# RGMII0_ETH_PHY.net
KiCad netlist of a schematic drawn in Altium Designer
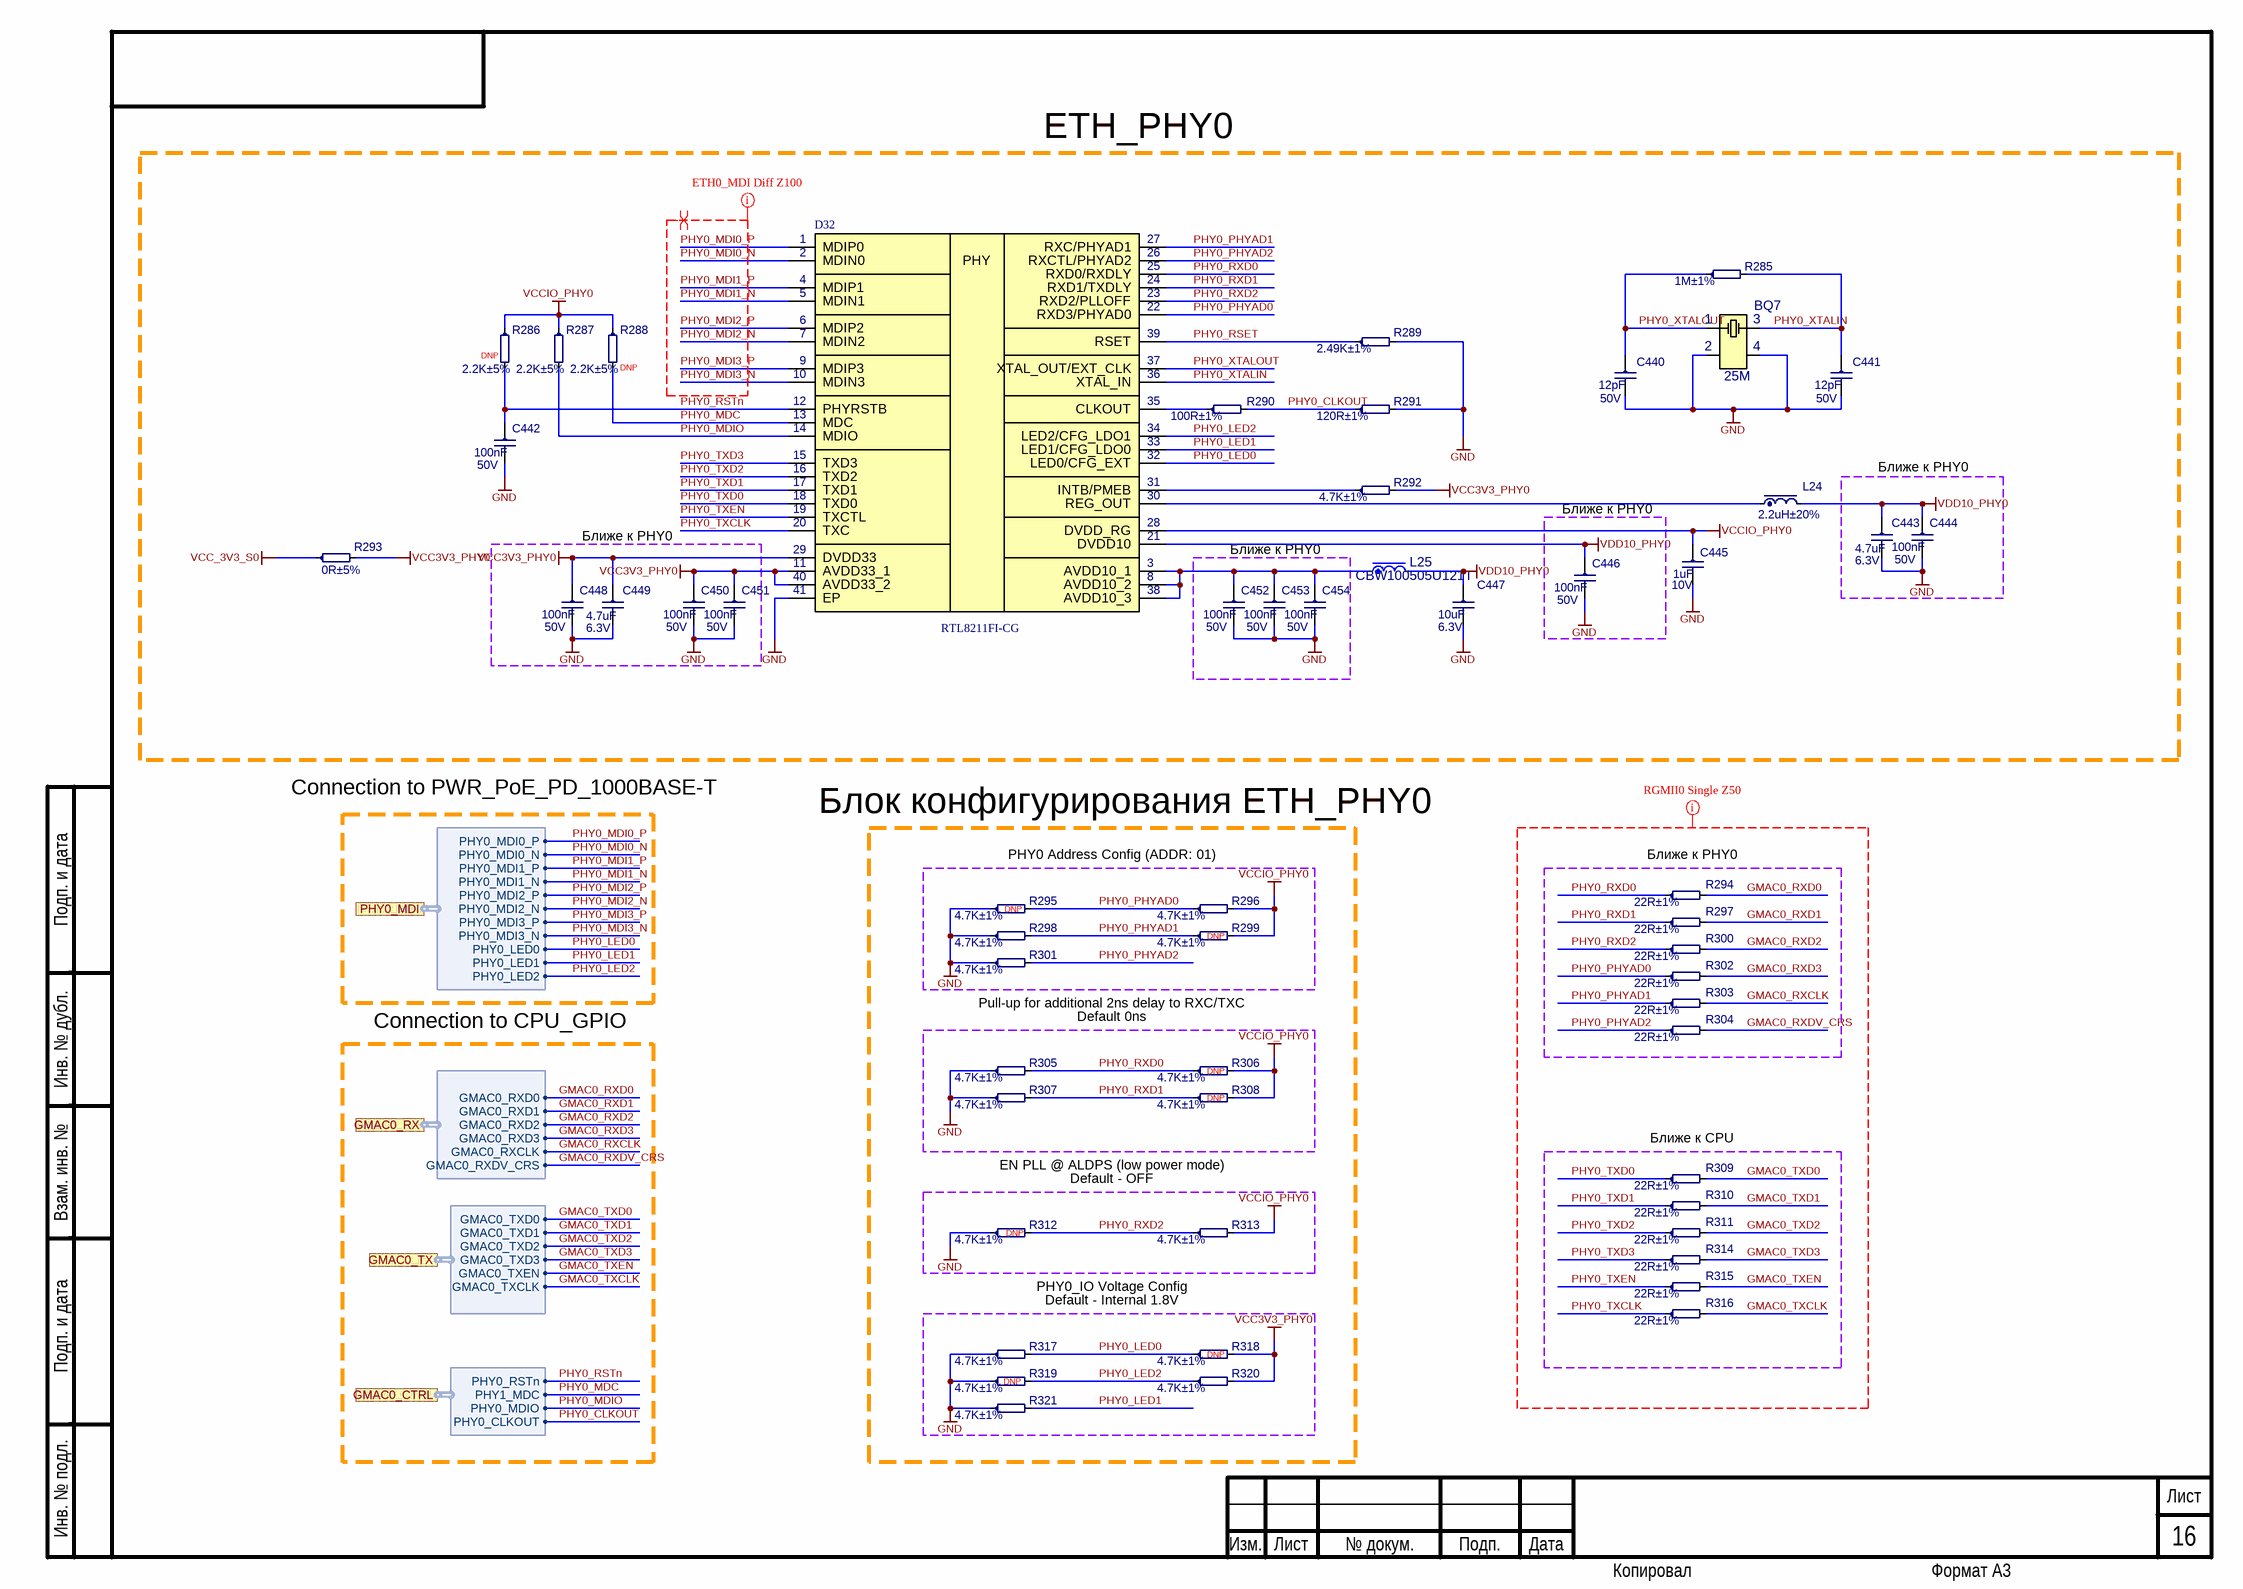
[diagram p0: RGMII0_ETH_PHY.SchDoc]

(export (version "E")
  (design (tool "Eeschema 10.0.6"))
  (components
    (comp (ref "BQ7")
      (value "25M")
      (footprint "NX3225GA")
      (description "25MHz 10pF ±10ppm SMD3225-4P")
      (fields (field (name "PART NUMBER") "TAXM25M4RDBCCT2T") (field (name "TOLERANCE") "10ppm"))
      (libsource (lib "ATB") (part "BQ_4pin_2closed_2.4_2.4"))
    )
    (comp (ref "C440")
      (value "12pF")
      (footprint "C0402")
      (fields
        (field (name "VOLTAGE") "50V")
        (field (name "PART NUMBER") "0402-NP0-50V-12pF±5%")
        (field (name "TOLERANCE") "5%")
        (field (name "MANUFACTURER") "Murata Electronics")
      )
      (libsource (lib "ATB") (part "C"))
    )
    (comp (ref "C441")
      (value "12pF")
      (footprint "C0402")
      (fields
        (field (name "VOLTAGE") "50V")
        (field (name "PART NUMBER") "0402-NP0-50V-12pF±5%")
        (field (name "TOLERANCE") "5%")
        (field (name "MANUFACTURER") "Murata Electronics")
      )
      (libsource (lib "ATB") (part "C"))
    )
    (comp (ref "C442")
      (value "100nF")
      (footprint "C0402")
      (description "Ceramic Capacitor 0402 100nF ±10% 50V X7R")
      (fields
        (field (name "VOLTAGE") "50V")
        (field (name "PART NUMBER") "0402-X7R-50V-0.1uF±10%")
        (field (name "TOLERANCE") "10%")
      )
      (libsource (lib "ATB") (part "C"))
    )
    (comp (ref "C443")
      (value "4.7uF")
      (footprint "C0402")
      (description "Ceramic Capacitor 0402 4.7uF ±20% 6.3V X5R")
      (fields
        (field (name "VOLTAGE") "6.3V")
        (field (name "PART NUMBER") "0402-X5R-6.3V-4.7uF±20%")
        (field (name "TOLERANCE") "20%")
      )
      (libsource (lib "ATB") (part "C"))
    )
    (comp (ref "C444")
      (value "100nF")
      (footprint "C0402")
      (description "Ceramic Capacitor 0402 100nF ±10% 50V X7R")
      (fields
        (field (name "VOLTAGE") "50V")
        (field (name "PART NUMBER") "0402-X7R-50V-0.1uF±10%")
        (field (name "TOLERANCE") "10%")
      )
      (libsource (lib "ATB") (part "C"))
    )
    (comp (ref "C445")
      (value "1uF")
      (footprint "C0402")
      (fields
        (field (name "VOLTAGE") "10V")
        (field (name "PART NUMBER") "0402-X5R-10V-1uF±10%")
        (field (name "TOLERANCE") "10%")
        (field (name "MANUFACTURER") "Samsung")
      )
      (libsource (lib "ATB") (part "C"))
    )
    (comp (ref "C446")
      (value "100nF")
      (footprint "C0402")
      (description "Ceramic Capacitor 0402 100nF ±10% 50V X7R")
      (fields
        (field (name "VOLTAGE") "50V")
        (field (name "PART NUMBER") "0402-X7R-50V-0.1uF±10%")
        (field (name "TOLERANCE") "10%")
      )
      (libsource (lib "ATB") (part "C"))
    )
    (comp (ref "C447")
      (value "10uF")
      (footprint "C0402")
      (fields
        (field (name "VOLTAGE") "6.3V")
        (field (name "PART NUMBER") "0402-X5R-6.3V-10uF±20%")
        (field (name "TOLERANCE") "20%")
        (field (name "MANUFACTURER") "Yageo")
      )
      (libsource (lib "ATB") (part "C"))
    )
    (comp (ref "C448")
      (value "100nF")
      (footprint "C0402")
      (description "Ceramic Capacitor 0402 100nF ±10% 50V X7R")
      (fields
        (field (name "VOLTAGE") "50V")
        (field (name "PART NUMBER") "0402-X7R-50V-0.1uF±10%")
        (field (name "TOLERANCE") "10%")
      )
      (libsource (lib "ATB") (part "C"))
    )
    (comp (ref "C449")
      (value "4.7uF")
      (footprint "C0402")
      (description "Ceramic Capacitor 0402 4.7uF ±20% 6.3V X5R")
      (fields
        (field (name "VOLTAGE") "6.3V")
        (field (name "PART NUMBER") "0402-X5R-6.3V-4.7uF±20%")
        (field (name "TOLERANCE") "20%")
      )
      (libsource (lib "ATB") (part "C"))
    )
    (comp (ref "C450")
      (value "100nF")
      (footprint "C0402")
      (description "Ceramic Capacitor 0402 100nF ±10% 50V X7R")
      (fields
        (field (name "VOLTAGE") "50V")
        (field (name "PART NUMBER") "0402-X7R-50V-0.1uF±10%")
        (field (name "TOLERANCE") "10%")
      )
      (libsource (lib "ATB") (part "C"))
    )
    (comp (ref "C451")
      (value "100nF")
      (footprint "C0402")
      (description "Ceramic Capacitor 0402 100nF ±10% 50V X7R")
      (fields
        (field (name "VOLTAGE") "50V")
        (field (name "PART NUMBER") "0402-X7R-50V-0.1uF±10%")
        (field (name "TOLERANCE") "10%")
      )
      (libsource (lib "ATB") (part "C"))
    )
    (comp (ref "C452")
      (value "100nF")
      (footprint "C0402")
      (description "Ceramic Capacitor 0402 100nF ±10% 50V X7R")
      (fields
        (field (name "VOLTAGE") "50V")
        (field (name "PART NUMBER") "0402-X7R-50V-0.1uF±10%")
        (field (name "TOLERANCE") "10%")
      )
      (libsource (lib "ATB") (part "C"))
    )
    (comp (ref "C453")
      (value "100nF")
      (footprint "C0402")
      (description "Ceramic Capacitor 0402 100nF ±10% 50V X7R")
      (fields
        (field (name "VOLTAGE") "50V")
        (field (name "PART NUMBER") "0402-X7R-50V-0.1uF±10%")
        (field (name "TOLERANCE") "10%")
      )
      (libsource (lib "ATB") (part "C"))
    )
    (comp (ref "C454")
      (value "100nF")
      (footprint "C0402")
      (description "Ceramic Capacitor 0402 100nF ±10% 50V X7R")
      (fields
        (field (name "VOLTAGE") "50V")
        (field (name "PART NUMBER") "0402-X7R-50V-0.1uF±10%")
        (field (name "TOLERANCE") "10%")
      )
      (libsource (lib "ATB") (part "C"))
    )
    (comp (ref "D32")
      (value "RTL8211FI-CG")
      (footprint "RTL8211F-CG")
      (description "Phy 1-CH 10MBPS/100MBPS/1GBPS 3.3V 40-PIN QFN")
      (fields (field (name "MANUFACTURER") "Realtek Semicon"))
      (libsource (lib "LIB_RK") (part "RTL8211F-CG"))
    )
    (comp (ref "L24")
      (value "2.2uH±20%")
      (footprint "L0806")
      (fields
        (field (name "PART NUMBER") "0806-2.1A-15uH±20%")
        (field (name "TOLERANCE") "20%")
        (field (name "MANUFACTURER") "Murata Electronics")
      )
      (libsource (lib "ATB") (part "L"))
    )
    (comp (ref "L25")
      (value "CBW100505U121T")
      (footprint "L0402")
      (description "120Ω@100MHz  Ferrite Beads")
      (fields (field (name "TOLERANCE") "25%") (field (name "MANUFACTURER") "Murata Electronics"))
      (libsource (lib "") (part "L_1"))
    )
    (comp (ref "R285")
      (value "1M±1%")
      (footprint "R0402")
      (description "Chip Resistor 0402 1MΩ ±1% 50V ±100ppm/℃ Thick Film")
      (fields (field (name "PART NUMBER") "0402-0.0625W-1M-100ppm±1%") (field (name "TOLERANCE") "1%"))
      (libsource (lib "ATB") (part "R"))
    )
    (comp (ref "R286")
      (value "2.2K±5%")
      (footprint "R0402")
      (fields
        (field (name "PART NUMBER") "0402-0.0625W-2.2K-100ppm±5%")
        (field (name "TOLERANCE") "5%")
        (field (name "MANUFACTURER") "Yageo")
      )
      (libsource (lib "ATB") (part "R"))
    )
    (comp (ref "R287")
      (value "2.2K±5%")
      (footprint "R0402")
      (fields
        (field (name "PART NUMBER") "0402-0.0625W-2.2K-100ppm±5%")
        (field (name "TOLERANCE") "5%")
        (field (name "MANUFACTURER") "Yageo")
      )
      (libsource (lib "ATB") (part "R"))
    )
    (comp (ref "R288")
      (value "2.2K±5%")
      (footprint "R0402")
      (fields
        (field (name "PART NUMBER") "0402-0.0625W-2.2K-100ppm±5%")
        (field (name "TOLERANCE") "5%")
        (field (name "MANUFACTURER") "Yageo")
      )
      (libsource (lib "ATB") (part "R"))
    )
    (comp (ref "R289")
      (value "2.49K±1%")
      (footprint "R0402")
      (description "Chip Resistor 0402 2.49kΩ ±1% 50V ±100ppm/℃ Thick Film")
      (fields (field (name "PART NUMBER") "0402-0.0625W-2.49K-100ppm±1%") (field (name "TOLERANCE") "1%"))
      (libsource (lib "ATB") (part "R"))
    )
    (comp (ref "R290")
      (value "100R±1%")
      (footprint "R0402")
      (description "Chip Resistor 0402 100Ω ±1% 50V ±100ppm/℃ Thick Film")
      (fields (field (name "PART NUMBER") "0402-0.0625W-100R-100ppm±1%") (field (name "TOLERANCE") "1%"))
      (libsource (lib "ATB") (part "R"))
    )
    (comp (ref "R291")
      (value "120R±1%")
      (footprint "R0402")
      (fields
        (field (name "PART NUMBER") "0402-0.0625W-120R-100ppm±1%")
        (field (name "TOLERANCE") "1%")
        (field (name "MANUFACTURER") "Yageo")
      )
      (libsource (lib "ATB") (part "R"))
    )
    (comp (ref "R292")
      (value "4.7K±1%")
      (footprint "R0402")
      (fields
        (field (name "PART NUMBER") "0402-0.0625W-4.7K-100ppm±1%")
        (field (name "TOLERANCE") "1%")
        (field (name "MANUFACTURER") "Yageo")
      )
      (libsource (lib "ATB") (part "R"))
    )
    (comp (ref "R293")
      (value "0R±5%")
      (footprint "R0805")
      (fields
        (field (name "PART NUMBER") "0805-0.125W-0R-250ppm±5%")
        (field (name "TOLERANCE") "5%")
        (field (name "MANUFACTURER") "Yageo")
      )
      (libsource (lib "ATB") (part "R"))
    )
    (comp (ref "R294")
      (value "22R±1%")
      (footprint "R0402")
      (description "Chip Resistor 0402 22Ω ±1% 50V ±100ppm/℃ Thick Film")
      (fields (field (name "PART NUMBER") "0402-0.0625W-22R-100ppm±1%") (field (name "TOLERANCE") "1%"))
      (libsource (lib "ATB") (part "R"))
    )
    (comp (ref "R295")
      (value "4.7K±1%")
      (footprint "R0402")
      (fields
        (field (name "PART NUMBER") "0402-0.0625W-4.7K-100ppm±1%")
        (field (name "TOLERANCE") "1%")
        (field (name "MANUFACTURER") "Yageo")
      )
      (libsource (lib "ATB") (part "R"))
    )
    (comp (ref "R296")
      (value "4.7K±1%")
      (footprint "R0402")
      (fields
        (field (name "PART NUMBER") "0402-0.0625W-4.7K-100ppm±1%")
        (field (name "TOLERANCE") "1%")
        (field (name "MANUFACTURER") "Yageo")
      )
      (libsource (lib "ATB") (part "R"))
    )
    (comp (ref "R297")
      (value "22R±1%")
      (footprint "R0402")
      (description "Chip Resistor 0402 22Ω ±1% 50V ±100ppm/℃ Thick Film")
      (fields (field (name "PART NUMBER") "0402-0.0625W-22R-100ppm±1%") (field (name "TOLERANCE") "1%"))
      (libsource (lib "ATB") (part "R"))
    )
    (comp (ref "R298")
      (value "4.7K±1%")
      (footprint "R0402")
      (fields
        (field (name "PART NUMBER") "0402-0.0625W-4.7K-100ppm±1%")
        (field (name "TOLERANCE") "1%")
        (field (name "MANUFACTURER") "Yageo")
      )
      (libsource (lib "ATB") (part "R"))
    )
    (comp (ref "R299")
      (value "4.7K±1%")
      (footprint "R0402")
      (fields
        (field (name "PART NUMBER") "0402-0.0625W-4.7K-100ppm±1%")
        (field (name "TOLERANCE") "1%")
        (field (name "MANUFACTURER") "Yageo")
      )
      (libsource (lib "ATB") (part "R"))
    )
    (comp (ref "R300")
      (value "22R±1%")
      (footprint "R0402")
      (description "Chip Resistor 0402 22Ω ±1% 50V ±100ppm/℃ Thick Film")
      (fields (field (name "PART NUMBER") "0402-0.0625W-22R-100ppm±1%") (field (name "TOLERANCE") "1%"))
      (libsource (lib "ATB") (part "R"))
    )
    (comp (ref "R301")
      (value "4.7K±1%")
      (footprint "R0402")
      (fields
        (field (name "PART NUMBER") "0402-0.0625W-4.7K-100ppm±1%")
        (field (name "TOLERANCE") "1%")
        (field (name "MANUFACTURER") "Yageo")
      )
      (libsource (lib "ATB") (part "R"))
    )
    (comp (ref "R302")
      (value "22R±1%")
      (footprint "R0402")
      (description "Chip Resistor 0402 22Ω ±1% 50V ±100ppm/℃ Thick Film")
      (fields (field (name "PART NUMBER") "0402-0.0625W-22R-100ppm±1%") (field (name "TOLERANCE") "1%"))
      (libsource (lib "ATB") (part "R"))
    )
    (comp (ref "R303")
      (value "22R±1%")
      (footprint "R0402")
      (description "Chip Resistor 0402 22Ω ±1% 50V ±100ppm/℃ Thick Film")
      (fields (field (name "PART NUMBER") "0402-0.0625W-22R-100ppm±1%") (field (name "TOLERANCE") "1%"))
      (libsource (lib "ATB") (part "R"))
    )
    (comp (ref "R304")
      (value "22R±1%")
      (footprint "R0402")
      (description "Chip Resistor 0402 22Ω ±1% 50V ±100ppm/℃ Thick Film")
      (fields (field (name "PART NUMBER") "0402-0.0625W-22R-100ppm±1%") (field (name "TOLERANCE") "1%"))
      (libsource (lib "ATB") (part "R"))
    )
    (comp (ref "R305")
      (value "4.7K±1%")
      (footprint "R0402")
      (fields
        (field (name "PART NUMBER") "0402-0.0625W-4.7K-100ppm±1%")
        (field (name "TOLERANCE") "1%")
        (field (name "MANUFACTURER") "Yageo")
      )
      (libsource (lib "ATB") (part "R"))
    )
    (comp (ref "R306")
      (value "4.7K±1%")
      (footprint "R0402")
      (fields
        (field (name "PART NUMBER") "0402-0.0625W-4.7K-100ppm±1%")
        (field (name "TOLERANCE") "1%")
        (field (name "MANUFACTURER") "Yageo")
      )
      (libsource (lib "ATB") (part "R"))
    )
    (comp (ref "R307")
      (value "4.7K±1%")
      (footprint "R0402")
      (fields
        (field (name "PART NUMBER") "0402-0.0625W-4.7K-100ppm±1%")
        (field (name "TOLERANCE") "1%")
        (field (name "MANUFACTURER") "Yageo")
      )
      (libsource (lib "ATB") (part "R"))
    )
    (comp (ref "R308")
      (value "4.7K±1%")
      (footprint "R0402")
      (fields
        (field (name "PART NUMBER") "0402-0.0625W-4.7K-100ppm±1%")
        (field (name "TOLERANCE") "1%")
        (field (name "MANUFACTURER") "Yageo")
      )
      (libsource (lib "ATB") (part "R"))
    )
    (comp (ref "R309")
      (value "22R±1%")
      (footprint "R0402")
      (description "Chip Resistor 0402 22Ω ±1% 50V ±100ppm/℃ Thick Film")
      (fields (field (name "PART NUMBER") "0402-0.0625W-22R-100ppm±1%") (field (name "TOLERANCE") "1%"))
      (libsource (lib "ATB") (part "R"))
    )
    (comp (ref "R310")
      (value "22R±1%")
      (footprint "R0402")
      (description "Chip Resistor 0402 22Ω ±1% 50V ±100ppm/℃ Thick Film")
      (fields (field (name "PART NUMBER") "0402-0.0625W-22R-100ppm±1%") (field (name "TOLERANCE") "1%"))
      (libsource (lib "ATB") (part "R"))
    )
    (comp (ref "R311")
      (value "22R±1%")
      (footprint "R0402")
      (description "Chip Resistor 0402 22Ω ±1% 50V ±100ppm/℃ Thick Film")
      (fields (field (name "PART NUMBER") "0402-0.0625W-22R-100ppm±1%") (field (name "TOLERANCE") "1%"))
      (libsource (lib "ATB") (part "R"))
    )
    (comp (ref "R312")
      (value "4.7K±1%")
      (footprint "R0402")
      (fields
        (field (name "PART NUMBER") "0402-0.0625W-4.7K-100ppm±1%")
        (field (name "TOLERANCE") "1%")
        (field (name "MANUFACTURER") "Yageo")
      )
      (libsource (lib "ATB") (part "R"))
    )
    (comp (ref "R313")
      (value "4.7K±1%")
      (footprint "R0402")
      (fields
        (field (name "PART NUMBER") "0402-0.0625W-4.7K-100ppm±1%")
        (field (name "TOLERANCE") "1%")
        (field (name "MANUFACTURER") "Yageo")
      )
      (libsource (lib "ATB") (part "R"))
    )
    (comp (ref "R314")
      (value "22R±1%")
      (footprint "R0402")
      (description "Chip Resistor 0402 22Ω ±1% 50V ±100ppm/℃ Thick Film")
      (fields (field (name "PART NUMBER") "0402-0.0625W-22R-100ppm±1%") (field (name "TOLERANCE") "1%"))
      (libsource (lib "ATB") (part "R"))
    )
    (comp (ref "R315")
      (value "22R±1%")
      (footprint "R0402")
      (description "Chip Resistor 0402 22Ω ±1% 50V ±100ppm/℃ Thick Film")
      (fields (field (name "PART NUMBER") "0402-0.0625W-22R-100ppm±1%") (field (name "TOLERANCE") "1%"))
      (libsource (lib "ATB") (part "R"))
    )
    (comp (ref "R316")
      (value "22R±1%")
      (footprint "R0402")
      (description "Chip Resistor 0402 22Ω ±1% 50V ±100ppm/℃ Thick Film")
      (fields (field (name "PART NUMBER") "0402-0.0625W-22R-100ppm±1%") (field (name "TOLERANCE") "1%"))
      (libsource (lib "ATB") (part "R"))
    )
    (comp (ref "R317")
      (value "4.7K±1%")
      (footprint "R0402")
      (fields
        (field (name "PART NUMBER") "0402-0.0625W-4.7K-100ppm±1%")
        (field (name "TOLERANCE") "1%")
        (field (name "MANUFACTURER") "Yageo")
      )
      (libsource (lib "ATB") (part "R"))
    )
    (comp (ref "R318")
      (value "4.7K±1%")
      (footprint "R0402")
      (fields
        (field (name "PART NUMBER") "0402-0.0625W-4.7K-100ppm±1%")
        (field (name "TOLERANCE") "1%")
        (field (name "MANUFACTURER") "Yageo")
      )
      (libsource (lib "ATB") (part "R"))
    )
    (comp (ref "R319")
      (value "4.7K±1%")
      (footprint "R0402")
      (fields
        (field (name "PART NUMBER") "0402-0.0625W-4.7K-100ppm±1%")
        (field (name "TOLERANCE") "1%")
        (field (name "MANUFACTURER") "Yageo")
      )
      (libsource (lib "ATB") (part "R"))
    )
    (comp (ref "R320")
      (value "4.7K±1%")
      (footprint "R0402")
      (fields
        (field (name "PART NUMBER") "0402-0.0625W-4.7K-100ppm±1%")
        (field (name "TOLERANCE") "1%")
        (field (name "MANUFACTURER") "Yageo")
      )
      (libsource (lib "ATB") (part "R"))
    )
    (comp (ref "R321")
      (value "4.7K±1%")
      (footprint "R0402")
      (fields
        (field (name "PART NUMBER") "0402-0.0625W-4.7K-100ppm±1%")
        (field (name "TOLERANCE") "1%")
        (field (name "MANUFACTURER") "Yageo")
      )
      (libsource (lib "ATB") (part "R"))
    )
  )
  (nets
    (net (code "5") (name "/GMAC0_RXCLK") (class "Default")
      (node (ref "R303") (pin "2") (pinfunction "2_2") (pintype "passive"))
    )
    (net (code "6") (name "/GMAC0_RXD0") (class "Default")
      (node (ref "R294") (pin "2") (pinfunction "2_2") (pintype "passive"))
    )
    (net (code "7") (name "/GMAC0_RXD1") (class "Default")
      (node (ref "R297") (pin "2") (pinfunction "2_2") (pintype "passive"))
    )
    (net (code "8") (name "/GMAC0_RXD2") (class "Default")
      (node (ref "R300") (pin "2") (pinfunction "2_2") (pintype "passive"))
    )
    (net (code "9") (name "/GMAC0_RXD3") (class "Default")
      (node (ref "R302") (pin "2") (pinfunction "2_2") (pintype "passive"))
    )
    (net (code "10") (name "/GMAC0_RXDV_CRS") (class "Default")
      (node (ref "R304") (pin "2") (pinfunction "2_2") (pintype "passive"))
    )
    (net (code "11") (name "/GMAC0_TXCLK") (class "Default")
      (node (ref "R316") (pin "2") (pinfunction "2_2") (pintype "passive"))
    )
    (net (code "12") (name "/GMAC0_TXD0") (class "Default")
      (node (ref "R309") (pin "2") (pinfunction "2_2") (pintype "passive"))
    )
    (net (code "13") (name "/GMAC0_TXD1") (class "Default")
      (node (ref "R310") (pin "2") (pinfunction "2_2") (pintype "passive"))
    )
    (net (code "14") (name "/GMAC0_TXD2") (class "Default")
      (node (ref "R311") (pin "2") (pinfunction "2_2") (pintype "passive"))
    )
    (net (code "15") (name "/GMAC0_TXD3") (class "Default")
      (node (ref "R314") (pin "2") (pinfunction "2_2") (pintype "passive"))
    )
    (net (code "16") (name "/GMAC0_TXEN") (class "Default")
      (node (ref "R315") (pin "2") (pinfunction "2_2") (pintype "passive"))
    )
    (net (code "17") (name "/PHY0_CLKOUT") (class "Default")
      (node (ref "R290") (pin "2") (pinfunction "2_2") (pintype "passive"))
      (node (ref "R291") (pin "1") (pinfunction "1_1") (pintype "passive"))
    )
    (net (code "18") (name "/PHY0_LED0") (class "Default")
      (node (ref "D32") (pin "32") (pinfunction "LED0/CFG_EXT_32") (pintype "passive"))
      (node (ref "R317") (pin "2") (pinfunction "2_2") (pintype "passive"))
      (node (ref "R318") (pin "1") (pinfunction "1_1") (pintype "passive"))
    )
    (net (code "19") (name "/PHY0_LED1") (class "Default")
      (node (ref "D32") (pin "33") (pinfunction "LED1/CFG_LDO0_33") (pintype "passive"))
      (node (ref "R321") (pin "2") (pinfunction "2_2") (pintype "passive"))
    )
    (net (code "20") (name "/PHY0_LED2") (class "Default")
      (node (ref "D32") (pin "34") (pinfunction "LED2/CFG_LDO1_34") (pintype "passive"))
      (node (ref "R319") (pin "2") (pinfunction "2_2") (pintype "passive"))
      (node (ref "R320") (pin "1") (pinfunction "1_1") (pintype "passive"))
    )
    (net (code "21") (name "/PHY0_MDC") (class "Default")
      (node (ref "D32") (pin "13") (pinfunction "MDC_13") (pintype "passive"))
      (node (ref "R288") (pin "2") (pinfunction "2_2") (pintype "passive"))
    )
    (net (code "22") (name "/PHY0_MDI0_N") (class "Default")
      (node (ref "D32") (pin "2") (pinfunction "MDIN0_2") (pintype "passive"))
    )
    (net (code "23") (name "/PHY0_MDI0_P") (class "Default")
      (node (ref "D32") (pin "1") (pinfunction "MDIP0_1") (pintype "passive"))
    )
    (net (code "24") (name "/PHY0_MDI1_N") (class "Default")
      (node (ref "D32") (pin "5") (pinfunction "MDIN1_5") (pintype "passive"))
    )
    (net (code "25") (name "/PHY0_MDI1_P") (class "Default")
      (node (ref "D32") (pin "4") (pinfunction "MDIP1_4") (pintype "passive"))
    )
    (net (code "26") (name "/PHY0_MDI2_N") (class "Default")
      (node (ref "D32") (pin "7") (pinfunction "MDIN2_7") (pintype "passive"))
    )
    (net (code "27") (name "/PHY0_MDI2_P") (class "Default")
      (node (ref "D32") (pin "6") (pinfunction "MDIP2_6") (pintype "passive"))
    )
    (net (code "28") (name "/PHY0_MDI3_N") (class "Default")
      (node (ref "D32") (pin "10") (pinfunction "MDIN3_10") (pintype "passive"))
    )
    (net (code "29") (name "/PHY0_MDI3_P") (class "Default")
      (node (ref "D32") (pin "9") (pinfunction "MDIP3_9") (pintype "passive"))
    )
    (net (code "30") (name "/PHY0_MDIO") (class "Default")
      (node (ref "D32") (pin "14") (pinfunction "MDIO_14") (pintype "passive"))
      (node (ref "R287") (pin "2") (pinfunction "2_2") (pintype "passive"))
    )
    (net (code "31") (name "/PHY0_PHYAD0") (class "Default")
      (node (ref "D32") (pin "22") (pinfunction "RXD3/PHYAD0_22") (pintype "passive"))
      (node (ref "R295") (pin "2") (pinfunction "2_2") (pintype "passive"))
      (node (ref "R296") (pin "1") (pinfunction "1_1") (pintype "passive"))
      (node (ref "R302") (pin "1") (pinfunction "1_1") (pintype "passive"))
    )
    (net (code "32") (name "/PHY0_PHYAD1") (class "Default")
      (node (ref "D32") (pin "27") (pinfunction "RXC/PHYAD1_27") (pintype "passive"))
      (node (ref "R298") (pin "2") (pinfunction "2_2") (pintype "passive"))
      (node (ref "R299") (pin "1") (pinfunction "1_1") (pintype "passive"))
      (node (ref "R303") (pin "1") (pinfunction "1_1") (pintype "passive"))
    )
    (net (code "33") (name "/PHY0_PHYAD2") (class "Default")
      (node (ref "D32") (pin "26") (pinfunction "RXCTL/PHYAD2_26") (pintype "passive"))
      (node (ref "R301") (pin "2") (pinfunction "2_2") (pintype "passive"))
      (node (ref "R304") (pin "1") (pinfunction "1_1") (pintype "passive"))
    )
    (net (code "34") (name "/PHY0_RSET") (class "Default")
      (node (ref "D32") (pin "39") (pinfunction "RSET_39") (pintype "passive"))
      (node (ref "R289") (pin "1") (pinfunction "1_1") (pintype "passive"))
    )
    (net (code "35") (name "/PHY0_RSTn") (class "Default")
      (node (ref "C442") (pin "1") (pinfunction "1_1") (pintype "passive"))
      (node (ref "D32") (pin "12") (pinfunction "PHYRSTB_12") (pintype "passive"))
      (node (ref "R286") (pin "2") (pinfunction "2_2") (pintype "passive"))
    )
    (net (code "36") (name "/PHY0_RXD0") (class "Default")
      (node (ref "D32") (pin "25") (pinfunction "RXD0/RXDLY_25") (pintype "passive"))
      (node (ref "R294") (pin "1") (pinfunction "1_1") (pintype "passive"))
      (node (ref "R305") (pin "2") (pinfunction "2_2") (pintype "passive"))
      (node (ref "R306") (pin "1") (pinfunction "1_1") (pintype "passive"))
    )
    (net (code "37") (name "/PHY0_RXD1") (class "Default")
      (node (ref "D32") (pin "24") (pinfunction "RXD1/TXDLY_24") (pintype "passive"))
      (node (ref "R297") (pin "1") (pinfunction "1_1") (pintype "passive"))
      (node (ref "R307") (pin "2") (pinfunction "2_2") (pintype "passive"))
      (node (ref "R308") (pin "1") (pinfunction "1_1") (pintype "passive"))
    )
    (net (code "38") (name "/PHY0_RXD2") (class "Default")
      (node (ref "D32") (pin "23") (pinfunction "RXD2/PLLOFF_23") (pintype "passive"))
      (node (ref "R300") (pin "1") (pinfunction "1_1") (pintype "passive"))
      (node (ref "R312") (pin "2") (pinfunction "2_2") (pintype "passive"))
      (node (ref "R313") (pin "1") (pinfunction "1_1") (pintype "passive"))
    )
    (net (code "39") (name "/PHY0_TXCLK") (class "Default")
      (node (ref "D32") (pin "20") (pinfunction "TXC_20") (pintype "passive"))
      (node (ref "R316") (pin "1") (pinfunction "1_1") (pintype "passive"))
    )
    (net (code "40") (name "/PHY0_TXD0") (class "Default")
      (node (ref "D32") (pin "18") (pinfunction "TXD0_18") (pintype "passive"))
      (node (ref "R309") (pin "1") (pinfunction "1_1") (pintype "passive"))
    )
    (net (code "41") (name "/PHY0_TXD1") (class "Default")
      (node (ref "D32") (pin "17") (pinfunction "TXD1_17") (pintype "passive"))
      (node (ref "R310") (pin "1") (pinfunction "1_1") (pintype "passive"))
    )
    (net (code "42") (name "/PHY0_TXD2") (class "Default")
      (node (ref "D32") (pin "16") (pinfunction "TXD2_16") (pintype "passive"))
      (node (ref "R311") (pin "1") (pinfunction "1_1") (pintype "passive"))
    )
    (net (code "43") (name "/PHY0_TXD3") (class "Default")
      (node (ref "D32") (pin "15") (pinfunction "TXD3_15") (pintype "passive"))
      (node (ref "R314") (pin "1") (pinfunction "1_1") (pintype "passive"))
    )
    (net (code "44") (name "/PHY0_TXEN") (class "Default")
      (node (ref "D32") (pin "19") (pinfunction "TXCTL_19") (pintype "passive"))
      (node (ref "R315") (pin "1") (pinfunction "1_1") (pintype "passive"))
    )
    (net (code "45") (name "/PHY0_XTALIN") (class "Default")
      (node (ref "BQ7") (pin "3") (pinfunction "3_3") (pintype "passive"))
      (node (ref "C441") (pin "1") (pinfunction "1_1") (pintype "passive"))
      (node (ref "D32") (pin "36") (pinfunction "XTAL_IN_36") (pintype "passive"))
      (node (ref "R285") (pin "2") (pinfunction "2_2") (pintype "passive"))
    )
    (net (code "46") (name "/PHY0_XTALOUT") (class "Default")
      (node (ref "BQ7") (pin "1") (pinfunction "1_1") (pintype "passive"))
      (node (ref "C440") (pin "1") (pinfunction "1_1") (pintype "passive"))
      (node (ref "D32") (pin "37") (pinfunction "XTAL_OUT/EXT_CLK_37") (pintype "passive"))
      (node (ref "R285") (pin "1") (pinfunction "1_1") (pintype "passive"))
    )
    (net (code "51") (name "GND") (class "Default")
      (node (ref "BQ7") (pin "2") (pinfunction "2_2") (pintype "passive"))
      (node (ref "BQ7") (pin "4") (pinfunction "4_4") (pintype "passive"))
      (node (ref "C440") (pin "2") (pinfunction "2_2") (pintype "passive"))
      (node (ref "C441") (pin "2") (pinfunction "2_2") (pintype "passive"))
      (node (ref "C442") (pin "2") (pinfunction "2_2") (pintype "passive"))
      (node (ref "C443") (pin "2") (pinfunction "2_2") (pintype "passive"))
      (node (ref "C444") (pin "2") (pinfunction "2_2") (pintype "passive"))
      (node (ref "C445") (pin "2") (pinfunction "2_2") (pintype "passive"))
      (node (ref "C446") (pin "2") (pinfunction "2_2") (pintype "passive"))
      (node (ref "C447") (pin "2") (pinfunction "2_2") (pintype "passive"))
      (node (ref "C448") (pin "2") (pinfunction "2_2") (pintype "passive"))
      (node (ref "C449") (pin "2") (pinfunction "2_2") (pintype "passive"))
      (node (ref "C450") (pin "2") (pinfunction "2_2") (pintype "passive"))
      (node (ref "C451") (pin "2") (pinfunction "2_2") (pintype "passive"))
      (node (ref "C452") (pin "2") (pinfunction "2_2") (pintype "passive"))
      (node (ref "C453") (pin "2") (pinfunction "2_2") (pintype "passive"))
      (node (ref "C454") (pin "2") (pinfunction "2_2") (pintype "passive"))
      (node (ref "D32") (pin "41") (pinfunction "EP_41") (pintype "passive"))
      (node (ref "R289") (pin "2") (pinfunction "2_2") (pintype "passive"))
      (node (ref "R291") (pin "2") (pinfunction "2_2") (pintype "passive"))
      (node (ref "R295") (pin "1") (pinfunction "1_1") (pintype "passive"))
      (node (ref "R298") (pin "1") (pinfunction "1_1") (pintype "passive"))
      (node (ref "R301") (pin "1") (pinfunction "1_1") (pintype "passive"))
      (node (ref "R305") (pin "1") (pinfunction "1_1") (pintype "passive"))
      (node (ref "R307") (pin "1") (pinfunction "1_1") (pintype "passive"))
      (node (ref "R312") (pin "1") (pinfunction "1_1") (pintype "passive"))
      (node (ref "R317") (pin "1") (pinfunction "1_1") (pintype "passive"))
      (node (ref "R319") (pin "1") (pinfunction "1_1") (pintype "passive"))
      (node (ref "R321") (pin "1") (pinfunction "1_1") (pintype "passive"))
    )
    (net (code "52") (name "Net-(D32-AVDD10_1)") (class "Default")
      (node (ref "C452") (pin "1") (pinfunction "1_1") (pintype "passive"))
      (node (ref "C453") (pin "1") (pinfunction "1_1") (pintype "passive"))
      (node (ref "C454") (pin "1") (pinfunction "1_1") (pintype "passive"))
      (node (ref "D32") (pin "3") (pinfunction "AVDD10_1_3") (pintype "passive"))
      (node (ref "D32") (pin "38") (pinfunction "AVDD10_3_38") (pintype "passive"))
      (node (ref "D32") (pin "8") (pinfunction "AVDD10_2_8") (pintype "passive"))
      (node (ref "L25") (pin "1") (pinfunction "1_1") (pintype "passive"))
    )
    (net (code "53") (name "Net-(D32-CLKOUT)") (class "Default")
      (node (ref "D32") (pin "35") (pinfunction "CLKOUT_35") (pintype "passive"))
      (node (ref "R290") (pin "1") (pinfunction "1_1") (pintype "passive"))
    )
    (net (code "54") (name "Net-(D32-INTB{slash}PMEB)") (class "Default")
      (node (ref "D32") (pin "31") (pinfunction "INTB/PMEB_31") (pintype "passive"))
      (node (ref "R292") (pin "1") (pinfunction "1_1") (pintype "passive"))
    )
    (net (code "55") (name "Net-(D32-REG_OUT)") (class "Default")
      (node (ref "D32") (pin "30") (pinfunction "REG_OUT_30") (pintype "passive"))
      (node (ref "L24") (pin "1") (pinfunction "1_1") (pintype "passive"))
    )
    (net (code "56") (name "VCC3V3_PHY0") (class "Default")
      (node (ref "C448") (pin "1") (pinfunction "1_1") (pintype "passive"))
      (node (ref "C449") (pin "1") (pinfunction "1_1") (pintype "passive"))
      (node (ref "C450") (pin "1") (pinfunction "1_1") (pintype "passive"))
      (node (ref "C451") (pin "1") (pinfunction "1_1") (pintype "passive"))
      (node (ref "D32") (pin "11") (pinfunction "AVDD33_1_11") (pintype "passive"))
      (node (ref "D32") (pin "29") (pinfunction "DVDD33_29") (pintype "passive"))
      (node (ref "D32") (pin "40") (pinfunction "AVDD33_2_40") (pintype "passive"))
      (node (ref "R292") (pin "2") (pinfunction "2_2") (pintype "passive"))
      (node (ref "R293") (pin "2") (pinfunction "2_2") (pintype "passive"))
      (node (ref "R318") (pin "2") (pinfunction "2_2") (pintype "passive"))
      (node (ref "R320") (pin "2") (pinfunction "2_2") (pintype "passive"))
    )
    (net (code "57") (name "VCCIO_PHY0") (class "Default")
      (node (ref "C445") (pin "1") (pinfunction "1_1") (pintype "passive"))
      (node (ref "D32") (pin "28") (pinfunction "DVDD_RG_28") (pintype "passive"))
      (node (ref "R286") (pin "1") (pinfunction "1_1") (pintype "passive"))
      (node (ref "R287") (pin "1") (pinfunction "1_1") (pintype "passive"))
      (node (ref "R288") (pin "1") (pinfunction "1_1") (pintype "passive"))
      (node (ref "R296") (pin "2") (pinfunction "2_2") (pintype "passive"))
      (node (ref "R299") (pin "2") (pinfunction "2_2") (pintype "passive"))
      (node (ref "R306") (pin "2") (pinfunction "2_2") (pintype "passive"))
      (node (ref "R308") (pin "2") (pinfunction "2_2") (pintype "passive"))
      (node (ref "R313") (pin "2") (pinfunction "2_2") (pintype "passive"))
    )
    (net (code "58") (name "VCC_3V3_S0") (class "Default")
      (node (ref "R293") (pin "1") (pinfunction "1_1") (pintype "passive"))
    )
    (net (code "59") (name "VDD10_PHY0") (class "Default")
      (node (ref "C443") (pin "1") (pinfunction "1_1") (pintype "passive"))
      (node (ref "C444") (pin "1") (pinfunction "1_1") (pintype "passive"))
      (node (ref "C446") (pin "1") (pinfunction "1_1") (pintype "passive"))
      (node (ref "C447") (pin "1") (pinfunction "1_1") (pintype "passive"))
      (node (ref "D32") (pin "21") (pinfunction "DVDD10_21") (pintype "passive"))
      (node (ref "L24") (pin "2") (pinfunction "2_2") (pintype "passive"))
      (node (ref "L25") (pin "2") (pinfunction "2_2") (pintype "passive"))
    )
  )
)
